# dv_power.net
KiCad netlist of a schematic drawn in Altium Designer
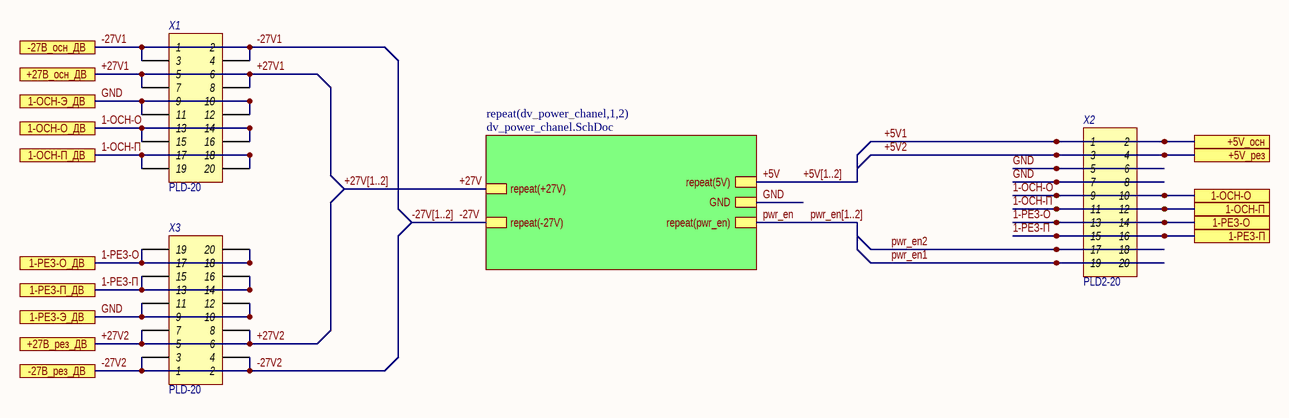
[diagram p0: dv_power.SchDoc]

(export (version "E")
  (design (tool "Eeschema 10.0.6"))
  (components
    (comp (ref "X1")
      (value "Header 2X20")
      (footprint "PBD-20")
      (description "Header, 20-Pin, Dual row")
      (fields (field (name "НАИМЕНОВАНИЕ") "PLD-20"))
      (libsource (lib "") (part "Header 2X20_1"))
    )
    (comp (ref "X2")
      (value "Header 2X20")
      (footprint "SD87340-20")
      (description "Header, 20-Pin, Dual row")
      (fields (field (name "НАИМЕНОВАНИЕ") "PLD2-20"))
      (libsource (lib "") (part "Header 2X20_1"))
    )
    (comp (ref "X3")
      (value "Header 2X20")
      (footprint "PBD-20")
      (description "Header, 20-Pin, Dual row")
      (fields (field (name "НАИМЕНОВАНИЕ") "PLD-20"))
      (libsource (lib "Connector") (part "Header 2X20"))
    )
  )
  (nets
    (net (code "2") (name "/+5V1") (class "Default")
      (node (ref "X2") (pin "1") (pinfunction "1_1") (pintype "passive"))
      (node (ref "X2") (pin "2") (pinfunction "2_2") (pintype "passive"))
    )
    (net (code "3") (name "/+5V2") (class "Default")
      (node (ref "X2") (pin "3") (pinfunction "3_3") (pintype "passive"))
      (node (ref "X2") (pin "4") (pinfunction "4_4") (pintype "passive"))
    )
    (net (code "5") (name "/+27V1") (class "Default")
      (node (ref "X1") (pin "5") (pinfunction "5_5") (pintype "passive"))
      (node (ref "X1") (pin "6") (pinfunction "6_6") (pintype "passive"))
      (node (ref "X1") (pin "7") (pinfunction "7_7") (pintype "passive"))
      (node (ref "X1") (pin "8") (pinfunction "8_8") (pintype "passive"))
    )
    (net (code "6") (name "/+27V2") (class "Default")
      (node (ref "X3") (pin "5") (pinfunction "5_5") (pintype "passive"))
      (node (ref "X3") (pin "6") (pinfunction "6_6") (pintype "passive"))
      (node (ref "X3") (pin "7") (pinfunction "7_7") (pintype "passive"))
      (node (ref "X3") (pin "8") (pinfunction "8_8") (pintype "passive"))
    )
    (net (code "9") (name "/-27V1") (class "Default")
      (node (ref "X1") (pin "1") (pinfunction "1_1") (pintype "passive"))
      (node (ref "X1") (pin "2") (pinfunction "2_2") (pintype "passive"))
      (node (ref "X1") (pin "3") (pinfunction "3_3") (pintype "passive"))
      (node (ref "X1") (pin "4") (pinfunction "4_4") (pintype "passive"))
    )
    (net (code "10") (name "/-27V2") (class "Default")
      (node (ref "X3") (pin "1") (pinfunction "1_1") (pintype "passive"))
      (node (ref "X3") (pin "2") (pinfunction "2_2") (pintype "passive"))
      (node (ref "X3") (pin "3") (pinfunction "3_3") (pintype "passive"))
      (node (ref "X3") (pin "4") (pinfunction "4_4") (pintype "passive"))
    )
    (net (code "12") (name "/1-ОСН-О") (class "Default")
      (node (ref "X1") (pin "13") (pinfunction "13_13") (pintype "passive"))
      (node (ref "X1") (pin "14") (pinfunction "14_14") (pintype "passive"))
      (node (ref "X1") (pin "15") (pinfunction "15_15") (pintype "passive"))
      (node (ref "X1") (pin "16") (pinfunction "16_16") (pintype "passive"))
      (node (ref "X2") (pin "10") (pinfunction "10_10") (pintype "passive"))
      (node (ref "X2") (pin "9") (pinfunction "9_9") (pintype "passive"))
    )
    (net (code "13") (name "/1-ОСН-П") (class "Default")
      (node (ref "X1") (pin "17") (pinfunction "17_17") (pintype "passive"))
      (node (ref "X1") (pin "18") (pinfunction "18_18") (pintype "passive"))
      (node (ref "X1") (pin "19") (pinfunction "19_19") (pintype "passive"))
      (node (ref "X1") (pin "20") (pinfunction "20_20") (pintype "passive"))
      (node (ref "X2") (pin "11") (pinfunction "11_11") (pintype "passive"))
      (node (ref "X2") (pin "12") (pinfunction "12_12") (pintype "passive"))
    )
    (net (code "14") (name "/1-РЕЗ-О") (class "Default")
      (node (ref "X2") (pin "13") (pinfunction "13_13") (pintype "passive"))
      (node (ref "X2") (pin "14") (pinfunction "14_14") (pintype "passive"))
      (node (ref "X3") (pin "17") (pinfunction "17_17") (pintype "passive"))
      (node (ref "X3") (pin "18") (pinfunction "18_18") (pintype "passive"))
      (node (ref "X3") (pin "19") (pinfunction "19_19") (pintype "passive"))
      (node (ref "X3") (pin "20") (pinfunction "20_20") (pintype "passive"))
    )
    (net (code "15") (name "/1-РЕЗ-П") (class "Default")
      (node (ref "X2") (pin "15") (pinfunction "15_15") (pintype "passive"))
      (node (ref "X2") (pin "16") (pinfunction "16_16") (pintype "passive"))
      (node (ref "X3") (pin "13") (pinfunction "13_13") (pintype "passive"))
      (node (ref "X3") (pin "14") (pinfunction "14_14") (pintype "passive"))
      (node (ref "X3") (pin "15") (pinfunction "15_15") (pintype "passive"))
      (node (ref "X3") (pin "16") (pinfunction "16_16") (pintype "passive"))
    )
    (net (code "16") (name "/GND") (class "Default")
      (node (ref "X1") (pin "10") (pinfunction "10_10") (pintype "passive"))
      (node (ref "X1") (pin "11") (pinfunction "11_11") (pintype "passive"))
      (node (ref "X1") (pin "12") (pinfunction "12_12") (pintype "passive"))
      (node (ref "X1") (pin "9") (pinfunction "9_9") (pintype "passive"))
      (node (ref "X2") (pin "5") (pinfunction "5_5") (pintype "passive"))
      (node (ref "X2") (pin "6") (pinfunction "6_6") (pintype "passive"))
      (node (ref "X2") (pin "7") (pinfunction "7_7") (pintype "passive"))
      (node (ref "X2") (pin "8") (pinfunction "8_8") (pintype "passive"))
      (node (ref "X3") (pin "10") (pinfunction "10_10") (pintype "passive"))
      (node (ref "X3") (pin "11") (pinfunction "11_11") (pintype "passive"))
      (node (ref "X3") (pin "12") (pinfunction "12_12") (pintype "passive"))
      (node (ref "X3") (pin "9") (pinfunction "9_9") (pintype "passive"))
    )
    (net (code "18") (name "/pwr_en1") (class "Default")
      (node (ref "X2") (pin "19") (pinfunction "19_19") (pintype "passive"))
      (node (ref "X2") (pin "20") (pinfunction "20_20") (pintype "passive"))
    )
    (net (code "19") (name "/pwr_en2") (class "Default")
      (node (ref "X2") (pin "17") (pinfunction "17_17") (pintype "passive"))
      (node (ref "X2") (pin "18") (pinfunction "18_18") (pintype "passive"))
    )
  )
)
